# buffered-mult.net
KiCad netlist of a schematic drawn in EAGLE
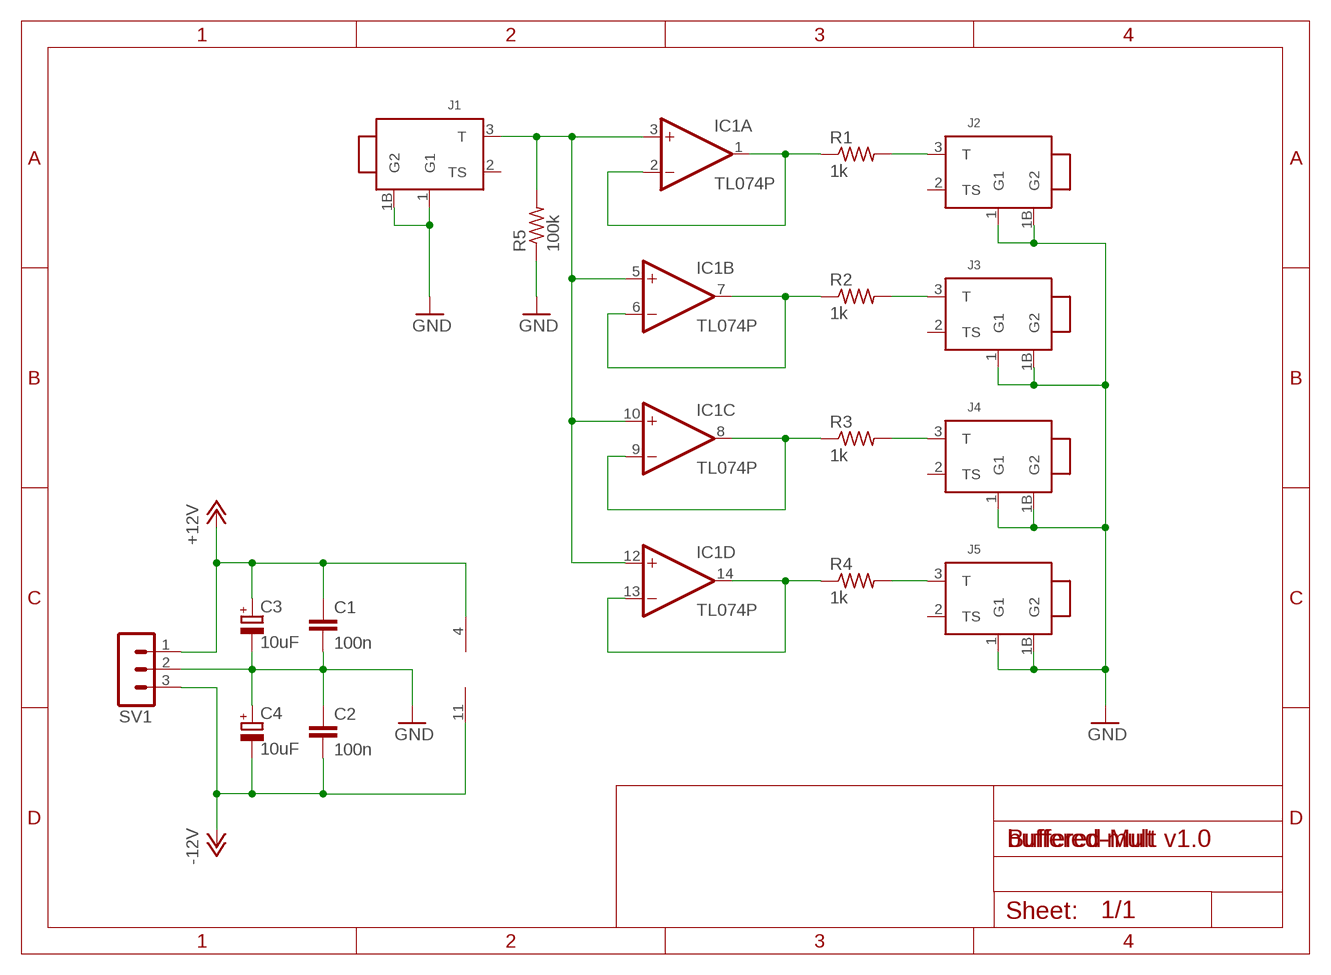
[diagram p0: schematic, sheet 1]

(export (version "E")
  (design (tool "Eeschema 10.0.6"))
  (components
    (comp (ref "C1")
      (value "100n")
      (footprint "eagle-import:C025-025X050")
      (libsource (lib "eagle-import") (part "C-EU025-025X050"))
    )
    (comp (ref "C2")
      (value "100n")
      (footprint "eagle-import:C025-025X050")
      (libsource (lib "eagle-import") (part "C-EU025-025X050"))
    )
    (comp (ref "C3")
      (value "10uF")
      (footprint "eagle-import:E2,5-6E")
      (libsource (lib "eagle-import") (part "CPOL-EUE2,5-6E"))
    )
    (comp (ref "C4")
      (value "10uF")
      (footprint "eagle-import:E2,5-6E")
      (libsource (lib "eagle-import") (part "CPOL-EUE2,5-6E"))
    )
    (comp (ref "IC1")
      (value "TL074P")
      (footprint "eagle-import:DIL14")
      (libsource (lib "eagle-import") (part "TL074P"))
    )
    (comp (ref "J1")
      (value "THONK_JACK")
      (footprint "eagle-import:THONK_JACK_P")
      (libsource (lib "eagle-import") (part "THONK_JACK"))
    )
    (comp (ref "J2")
      (value "THONK_JACK")
      (footprint "eagle-import:THONK_JACK_P")
      (libsource (lib "eagle-import") (part "THONK_JACK"))
    )
    (comp (ref "J3")
      (value "THONK_JACK")
      (footprint "eagle-import:THONK_JACK_P")
      (libsource (lib "eagle-import") (part "THONK_JACK"))
    )
    (comp (ref "J4")
      (value "THONK_JACK")
      (footprint "eagle-import:THONK_JACK_P")
      (libsource (lib "eagle-import") (part "THONK_JACK"))
    )
    (comp (ref "J5")
      (value "THONK_JACK")
      (footprint "eagle-import:THONK_JACK_P")
      (libsource (lib "eagle-import") (part "THONK_JACK"))
    )
    (comp (ref "R1")
      (value "1k")
      (footprint "eagle-import:0207_10")
      (libsource (lib "eagle-import") (part "R-US_0207/10"))
    )
    (comp (ref "R2")
      (value "1k")
      (footprint "eagle-import:0207_10")
      (libsource (lib "eagle-import") (part "R-US_0207/10"))
    )
    (comp (ref "R3")
      (value "1k")
      (footprint "eagle-import:0207_10")
      (libsource (lib "eagle-import") (part "R-US_0207/10"))
    )
    (comp (ref "R4")
      (value "1k")
      (footprint "eagle-import:0207_10")
      (libsource (lib "eagle-import") (part "R-US_0207/10"))
    )
    (comp (ref "R5")
      (value "100k")
      (footprint "eagle-import:0207_10")
      (libsource (lib "eagle-import") (part "R-US_0207/10"))
    )
    (comp (ref "SV1")
      (value "MA03-1")
      (footprint "eagle-import:MA03-1")
      (libsource (lib "eagle-import") (part "MA03-1"))
    )
  )
  (nets
    (net (code "1") (name "+12V") (class "Default")
      (node (ref "C1") (pin "1") (pinfunction "1_1") (pintype "passive"))
      (node (ref "C3") (pin "+") (pinfunction "+_+") (pintype "passive"))
      (node (ref "IC1") (pin "4") (pinfunction "V+_4") (pintype "power_in"))
      (node (ref "SV1") (pin "1") (pinfunction "1_1") (pintype "passive"))
    )
    (net (code "2") (name "-12V") (class "Default")
      (node (ref "C2") (pin "2") (pinfunction "2_2") (pintype "passive"))
      (node (ref "C4") (pin "-") (pinfunction "-_-") (pintype "passive"))
      (node (ref "IC1") (pin "11") (pinfunction "V-_11") (pintype "power_in"))
      (node (ref "SV1") (pin "3") (pinfunction "3_3") (pintype "passive"))
    )
    (net (code "3") (name "GND") (class "Default")
      (node (ref "C1") (pin "2") (pinfunction "2_2") (pintype "passive"))
      (node (ref "C2") (pin "1") (pinfunction "1_1") (pintype "passive"))
      (node (ref "C3") (pin "-") (pinfunction "-_-") (pintype "passive"))
      (node (ref "C4") (pin "+") (pinfunction "+_+") (pintype "passive"))
      (node (ref "J1") (pin "1") (pinfunction "G1_1") (pintype "bidirectional"))
      (node (ref "J1") (pin "1B") (pinfunction "G2_1B") (pintype "bidirectional"))
      (node (ref "J2") (pin "1") (pinfunction "G1_1") (pintype "bidirectional"))
      (node (ref "J2") (pin "1B") (pinfunction "G2_1B") (pintype "bidirectional"))
      (node (ref "J3") (pin "1") (pinfunction "G1_1") (pintype "bidirectional"))
      (node (ref "J3") (pin "1B") (pinfunction "G2_1B") (pintype "bidirectional"))
      (node (ref "J4") (pin "1") (pinfunction "G1_1") (pintype "bidirectional"))
      (node (ref "J4") (pin "1B") (pinfunction "G2_1B") (pintype "bidirectional"))
      (node (ref "J5") (pin "1") (pinfunction "G1_1") (pintype "bidirectional"))
      (node (ref "J5") (pin "1B") (pinfunction "G2_1B") (pintype "bidirectional"))
      (node (ref "R5") (pin "1") (pinfunction "1_1") (pintype "passive"))
      (node (ref "SV1") (pin "2") (pinfunction "2_2") (pintype "passive"))
    )
    (net (code "4") (name "Net-(IC1A-+IN)") (class "Default")
      (node (ref "IC1") (pin "10") (pinfunction "+IN_10") (pintype "input"))
      (node (ref "IC1") (pin "12") (pinfunction "+IN_12") (pintype "input"))
      (node (ref "IC1") (pin "3") (pinfunction "+IN_3") (pintype "input"))
      (node (ref "IC1") (pin "5") (pinfunction "+IN_5") (pintype "input"))
      (node (ref "J1") (pin "3") (pinfunction "T_3") (pintype "bidirectional"))
      (node (ref "R5") (pin "2") (pinfunction "2_2") (pintype "passive"))
    )
    (net (code "5") (name "Net-(IC1A--IN)") (class "Default")
      (node (ref "IC1") (pin "1") (pinfunction "OUT_1") (pintype "output"))
      (node (ref "IC1") (pin "2") (pinfunction "-IN_2") (pintype "input"))
      (node (ref "R1") (pin "1") (pinfunction "1_1") (pintype "passive"))
    )
    (net (code "6") (name "Net-(IC1B--IN)") (class "Default")
      (node (ref "IC1") (pin "6") (pinfunction "-IN_6") (pintype "input"))
      (node (ref "IC1") (pin "7") (pinfunction "OUT_7") (pintype "output"))
      (node (ref "R2") (pin "1") (pinfunction "1_1") (pintype "passive"))
    )
    (net (code "7") (name "Net-(IC1C--IN)") (class "Default")
      (node (ref "IC1") (pin "8") (pinfunction "OUT_8") (pintype "output"))
      (node (ref "IC1") (pin "9") (pinfunction "-IN_9") (pintype "input"))
      (node (ref "R3") (pin "1") (pinfunction "1_1") (pintype "passive"))
    )
    (net (code "8") (name "Net-(IC1D--IN)") (class "Default")
      (node (ref "IC1") (pin "13") (pinfunction "-IN_13") (pintype "input"))
      (node (ref "IC1") (pin "14") (pinfunction "OUT_14") (pintype "output"))
      (node (ref "R4") (pin "1") (pinfunction "1_1") (pintype "passive"))
    )
    (net (code "9") (name "Net-(J2-T)") (class "Default")
      (node (ref "J2") (pin "3") (pinfunction "T_3") (pintype "bidirectional"))
      (node (ref "R1") (pin "2") (pinfunction "2_2") (pintype "passive"))
    )
    (net (code "10") (name "Net-(J3-T)") (class "Default")
      (node (ref "J3") (pin "3") (pinfunction "T_3") (pintype "bidirectional"))
      (node (ref "R2") (pin "2") (pinfunction "2_2") (pintype "passive"))
    )
    (net (code "11") (name "Net-(J4-T)") (class "Default")
      (node (ref "J4") (pin "3") (pinfunction "T_3") (pintype "bidirectional"))
      (node (ref "R3") (pin "2") (pinfunction "2_2") (pintype "passive"))
    )
    (net (code "12") (name "Net-(J5-T)") (class "Default")
      (node (ref "J5") (pin "3") (pinfunction "T_3") (pintype "bidirectional"))
      (node (ref "R4") (pin "2") (pinfunction "2_2") (pintype "passive"))
    )
    (net (code "13") (name "unconnected-(J1-TS-Pad2)") (class "Default")
      (node (ref "J1") (pin "2") (pinfunction "TS_2") (pintype "bidirectional"))
    )
    (net (code "14") (name "unconnected-(J2-TS-Pad2)") (class "Default")
      (node (ref "J2") (pin "2") (pinfunction "TS_2") (pintype "bidirectional"))
    )
    (net (code "15") (name "unconnected-(J3-TS-Pad2)") (class "Default")
      (node (ref "J3") (pin "2") (pinfunction "TS_2") (pintype "bidirectional"))
    )
    (net (code "16") (name "unconnected-(J4-TS-Pad2)") (class "Default")
      (node (ref "J4") (pin "2") (pinfunction "TS_2") (pintype "bidirectional"))
    )
    (net (code "17") (name "unconnected-(J5-TS-Pad2)") (class "Default")
      (node (ref "J5") (pin "2") (pinfunction "TS_2") (pintype "bidirectional"))
    )
  )
)
